# sync.net
KiCad netlist of a schematic drawn in Altium Designer
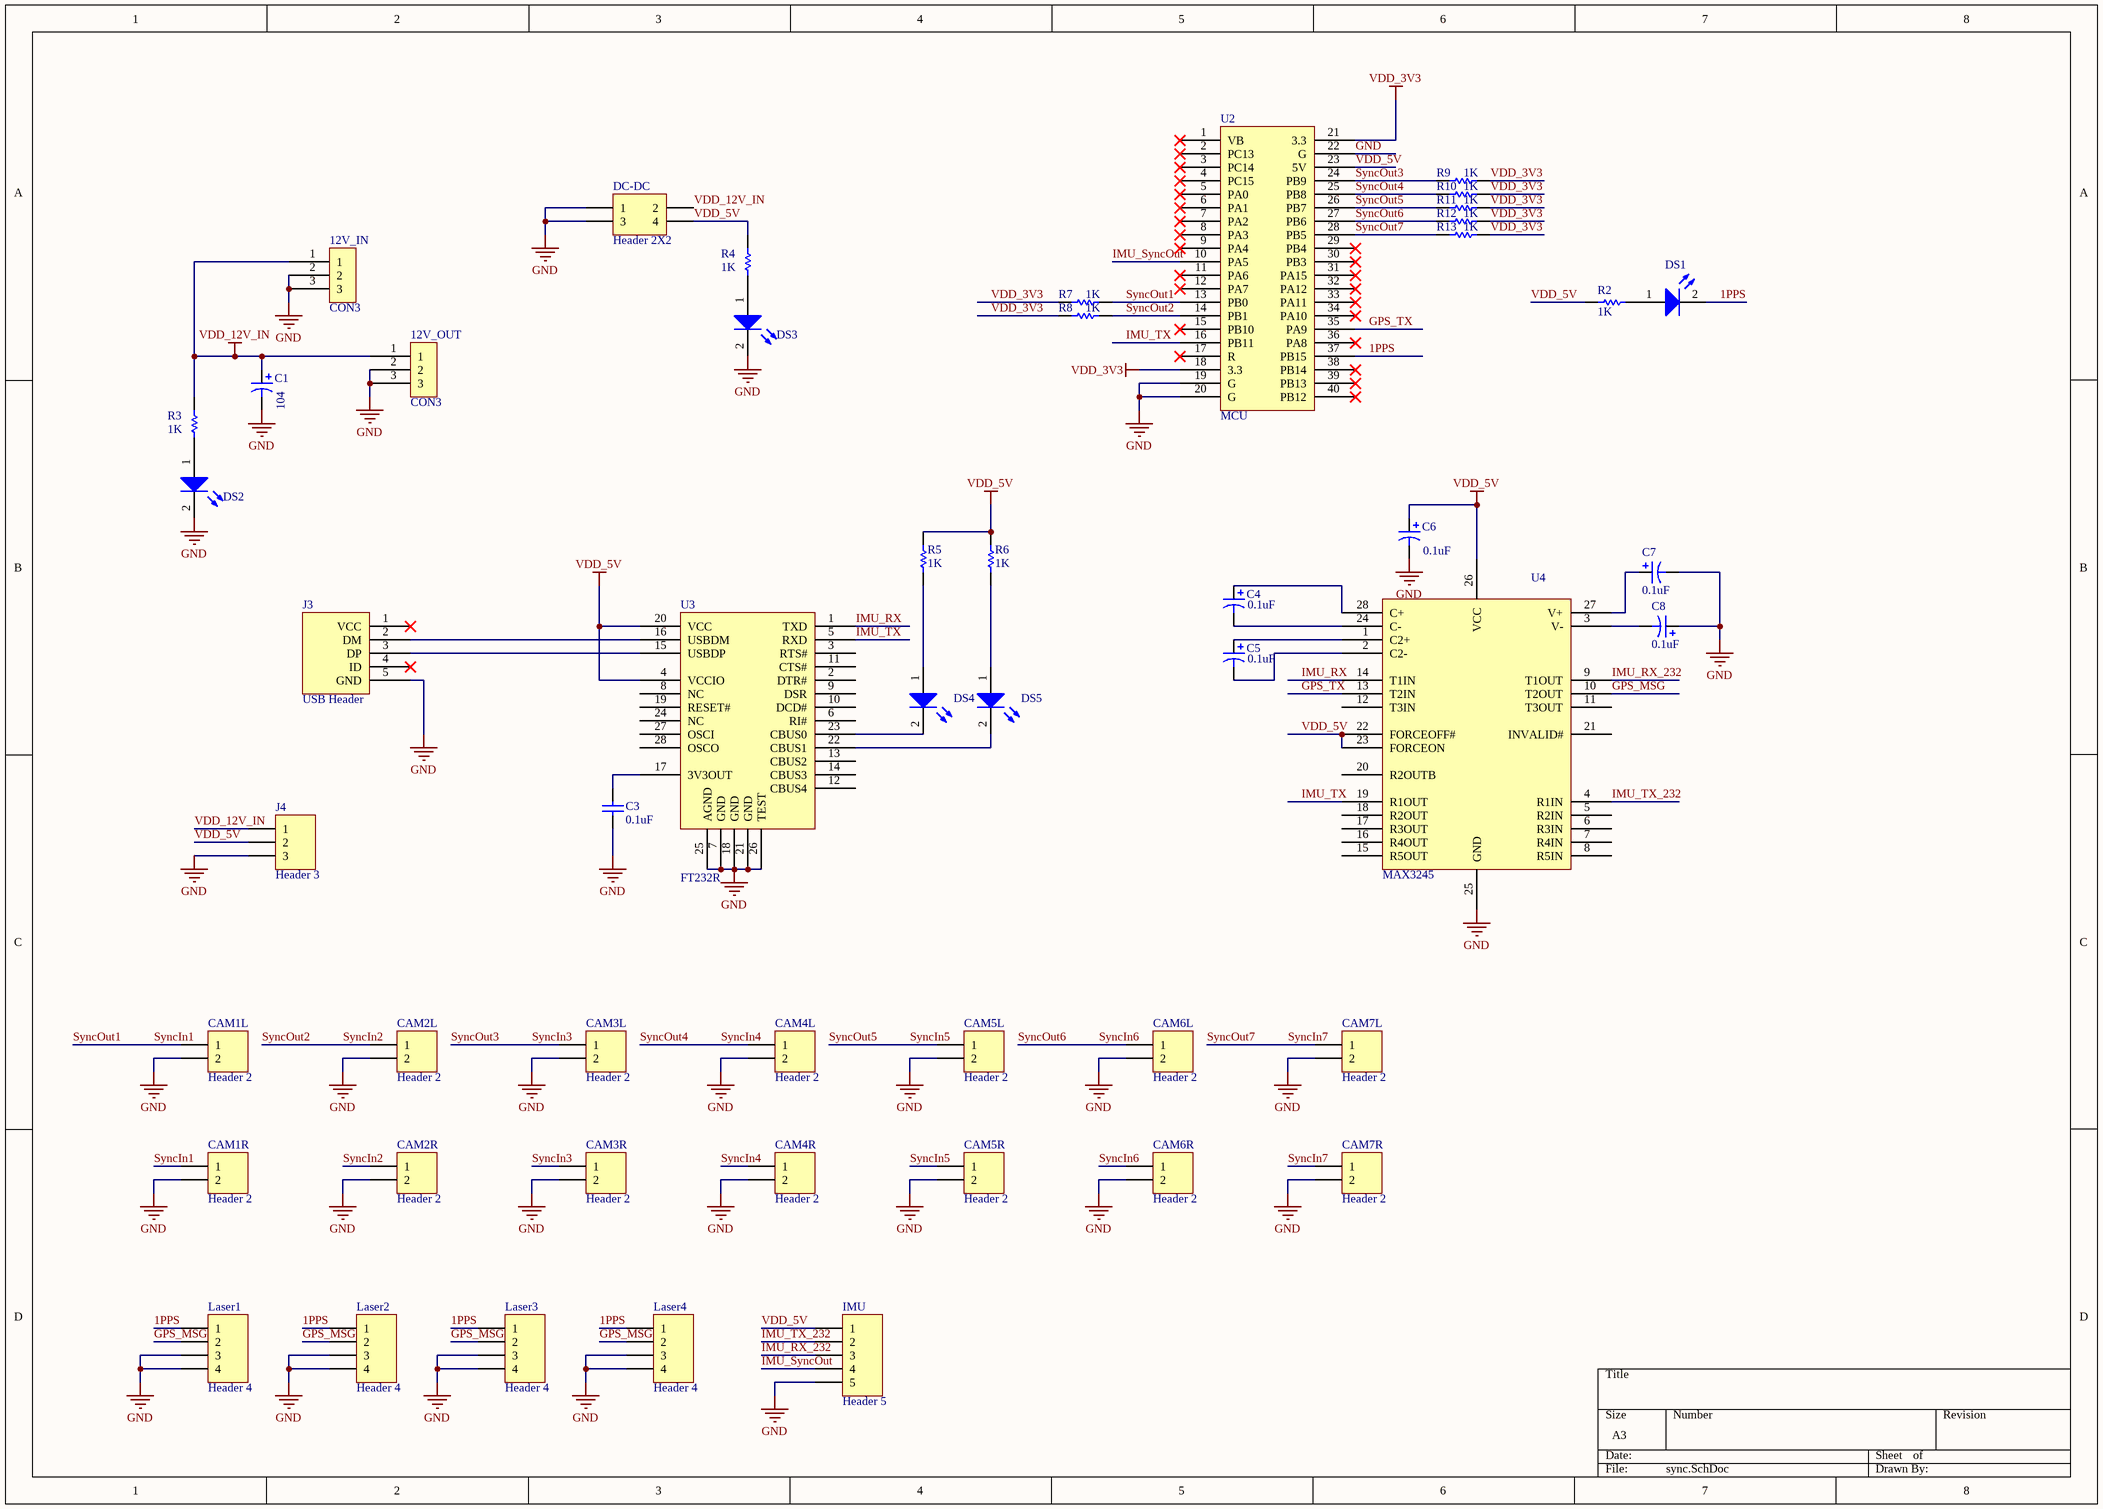
[diagram p0: sync.SchDoc]

(export (version "E")
  (design (tool "Eeschema 10.0.6"))
  (components
    (comp (ref "12V_IN")
      (value "CON3")
      (footprint "PW_PORT")
      (libsource (lib "Miscellaneous Connectors") (part "CON3"))
    )
    (comp (ref "12V_OUT") (value "CON3") (footprint "PW_PORT") (libsource (lib "EP3C25") (part "CON3")))
    (comp (ref "C1")
      (value "104")
      (footprint "0805")
      (description "Polarized Capacitor (Surface Mount)")
      (fields (field (name "PUBLISHER") "Altium Limited"))
      (libsource (lib "Miscellaneous Devices") (part "Cap Pol3"))
    )
    (comp (ref "C3")
      (value "0.1uF")
      (footprint "0805C")
      (description "Capacitor")
      (fields (field (name "PUBLISHER") "Altium Limited"))
      (libsource (lib "Miscellaneous Devices") (part "Cap"))
    )
    (comp (ref "C4")
      (value "0.1uF")
      (footprint "C1206")
      (description "Polarized Capacitor (Surface Mount)")
      (fields (field (name "PUBLISHER") "Altium Limited"))
      (libsource (lib "Miscellaneous Devices") (part "Cap Pol3"))
    )
    (comp (ref "C5")
      (value "0.1uF")
      (footprint "C1206")
      (description "Polarized Capacitor (Surface Mount)")
      (fields (field (name "PUBLISHER") "Altium Limited"))
      (libsource (lib "Miscellaneous Devices") (part "Cap Pol3"))
    )
    (comp (ref "C6")
      (value "0.1uF")
      (footprint "C1206")
      (description "Polarized Capacitor (Surface Mount)")
      (fields (field (name "PUBLISHER") "Altium Limited"))
      (libsource (lib "Miscellaneous Devices") (part "Cap Pol3"))
    )
    (comp (ref "C7")
      (value "0.1uF")
      (footprint "C1206")
      (description "Polarized Capacitor (Surface Mount)")
      (fields (field (name "PUBLISHER") "Altium Limited"))
      (libsource (lib "Miscellaneous Devices") (part "Cap Pol3"))
    )
    (comp (ref "C8")
      (value "0.1uF")
      (footprint "C1206")
      (description "Polarized Capacitor (Surface Mount)")
      (fields (field (name "PUBLISHER") "Altium Limited"))
      (libsource (lib "Miscellaneous Devices") (part "Cap Pol3"))
    )
    (comp (ref "CAM1L")
      (value "Header 2")
      (footprint "1.25mmP2")
      (description "Header, 2-Pin")
      (fields (field (name "PUBLISHER") "Altium Limited"))
      (libsource (lib "Miscellaneous Connectors") (part "Header 2"))
    )
    (comp (ref "CAM1R")
      (value "Header 2")
      (footprint "1.25mmP2")
      (description "Header, 2-Pin")
      (fields (field (name "PUBLISHER") "Altium Limited"))
      (libsource (lib "Miscellaneous Connectors") (part "Header 2"))
    )
    (comp (ref "CAM2L")
      (value "Header 2")
      (footprint "1.25mmP2")
      (description "Header, 2-Pin")
      (fields (field (name "PUBLISHER") "Altium Limited"))
      (libsource (lib "Miscellaneous Connectors") (part "Header 2"))
    )
    (comp (ref "CAM2R")
      (value "Header 2")
      (footprint "1.25mmP2")
      (description "Header, 2-Pin")
      (fields (field (name "PUBLISHER") "Altium Limited"))
      (libsource (lib "Miscellaneous Connectors") (part "Header 2"))
    )
    (comp (ref "CAM3L")
      (value "Header 2")
      (footprint "1.25mmP2")
      (description "Header, 2-Pin")
      (fields (field (name "PUBLISHER") "Altium Limited"))
      (libsource (lib "Miscellaneous Connectors") (part "Header 2"))
    )
    (comp (ref "CAM3R")
      (value "Header 2")
      (footprint "1.25mmP2")
      (description "Header, 2-Pin")
      (fields (field (name "PUBLISHER") "Altium Limited"))
      (libsource (lib "Miscellaneous Connectors") (part "Header 2"))
    )
    (comp (ref "CAM4L")
      (value "Header 2")
      (footprint "1.25mmP2")
      (description "Header, 2-Pin")
      (fields (field (name "PUBLISHER") "Altium Limited"))
      (libsource (lib "Miscellaneous Connectors") (part "Header 2"))
    )
    (comp (ref "CAM4R")
      (value "Header 2")
      (footprint "1.25mmP2")
      (description "Header, 2-Pin")
      (fields (field (name "PUBLISHER") "Altium Limited"))
      (libsource (lib "Miscellaneous Connectors") (part "Header 2"))
    )
    (comp (ref "CAM5L")
      (value "Header 2")
      (footprint "1.25mmP2")
      (description "Header, 2-Pin")
      (fields (field (name "PUBLISHER") "Altium Limited"))
      (libsource (lib "Miscellaneous Connectors") (part "Header 2"))
    )
    (comp (ref "CAM5R")
      (value "Header 2")
      (footprint "1.25mmP2")
      (description "Header, 2-Pin")
      (fields (field (name "PUBLISHER") "Altium Limited"))
      (libsource (lib "Miscellaneous Connectors") (part "Header 2"))
    )
    (comp (ref "CAM6L")
      (value "Header 2")
      (footprint "1.25mmP2")
      (description "Header, 2-Pin")
      (fields (field (name "PUBLISHER") "Altium Limited"))
      (libsource (lib "Miscellaneous Connectors") (part "Header 2"))
    )
    (comp (ref "CAM6R")
      (value "Header 2")
      (footprint "1.25mmP2")
      (description "Header, 2-Pin")
      (fields (field (name "PUBLISHER") "Altium Limited"))
      (libsource (lib "Miscellaneous Connectors") (part "Header 2"))
    )
    (comp (ref "CAM7L")
      (value "Header 2")
      (footprint "1.25mmP2")
      (description "Header, 2-Pin")
      (fields (field (name "PUBLISHER") "Altium Limited"))
      (libsource (lib "Miscellaneous Connectors") (part "Header 2"))
    )
    (comp (ref "CAM7R")
      (value "Header 2")
      (footprint "1.25mmP2")
      (description "Header, 2-Pin")
      (fields (field (name "PUBLISHER") "Altium Limited"))
      (libsource (lib "Miscellaneous Connectors") (part "Header 2"))
    )
    (comp (ref "DC-DC")
      (value "Header 2X2")
      (footprint "DC-DC5V_HDR2*2")
      (description "Header, 2-Pin, Dual row")
      (fields (field (name "PUBLISHER") "Altium Limited"))
      (libsource (lib "Miscellaneous Connectors") (part "Header 2X2"))
    )
    (comp (ref "DS1")
      (value "LED2")
      (footprint "0805D")
      (description "Typical RED, GREEN, YELLOW, AMBER GaAs LED")
      (fields
        (field (name "MANUFACTURER") "Generic Components")
        (field (name "PUBLISHER") "Altium Hobart Technology Centre")
      )
      (libsource (lib "Miscellaneous Devices") (part "LED2"))
    )
    (comp (ref "DS2")
      (value "LED2")
      (footprint "0805D")
      (description "Typical RED, GREEN, YELLOW, AMBER GaAs LED")
      (fields
        (field (name "MANUFACTURER") "Generic Components")
        (field (name "PUBLISHER") "Altium Hobart Technology Centre")
      )
      (libsource (lib "Miscellaneous Devices") (part "LED2"))
    )
    (comp (ref "DS3")
      (value "LED2")
      (footprint "0805D")
      (description "Typical RED, GREEN, YELLOW, AMBER GaAs LED")
      (fields
        (field (name "MANUFACTURER") "Generic Components")
        (field (name "PUBLISHER") "Altium Hobart Technology Centre")
      )
      (libsource (lib "Miscellaneous Devices") (part "LED2"))
    )
    (comp (ref "DS4")
      (value "LED2")
      (footprint "0805D")
      (description "Typical RED, GREEN, YELLOW, AMBER GaAs LED")
      (fields
        (field (name "MANUFACTURER") "Generic Components")
        (field (name "PUBLISHER") "Altium Hobart Technology Centre")
      )
      (libsource (lib "Miscellaneous Devices") (part "LED2"))
    )
    (comp (ref "DS5")
      (value "LED2")
      (footprint "0805D")
      (description "Typical RED, GREEN, YELLOW, AMBER GaAs LED")
      (fields
        (field (name "MANUFACTURER") "Generic Components")
        (field (name "PUBLISHER") "Altium Hobart Technology Centre")
      )
      (libsource (lib "Miscellaneous Devices") (part "LED2"))
    )
    (comp (ref "IMU")
      (value "Header 5")
      (footprint "1.25mmP5")
      (description "Header, 5-Pin")
      (fields (field (name "PUBLISHER") "Altium Limited"))
      (libsource (lib "Miscellaneous Connectors") (part "Header 5"))
    )
    (comp (ref "J3") (value "USB Header") (footprint "USB0.65-5") (libsource (lib "USB") (part "USB")))
    (comp (ref "J4")
      (value "Header 3")
      (footprint "HDR1X3")
      (description "Header, 3-Pin")
      (fields (field (name "PUBLISHER") "Altium Limited"))
      (libsource (lib "Miscellaneous Connectors") (part "Header 3"))
    )
    (comp (ref "Laser1")
      (value "Header 4")
      (footprint "1.25mmP4")
      (description "Header, 4-Pin")
      (fields (field (name "PUBLISHER") "Altium Limited"))
      (libsource (lib "Miscellaneous Connectors") (part "Header 4"))
    )
    (comp (ref "Laser2")
      (value "Header 4")
      (footprint "1.25mmP4")
      (description "Header, 4-Pin")
      (fields (field (name "PUBLISHER") "Altium Limited"))
      (libsource (lib "Miscellaneous Connectors") (part "Header 4"))
    )
    (comp (ref "Laser3")
      (value "Header 4")
      (footprint "1.25mmP4")
      (description "Header, 4-Pin")
      (fields (field (name "PUBLISHER") "Altium Limited"))
      (libsource (lib "Miscellaneous Connectors") (part "Header 4"))
    )
    (comp (ref "Laser4")
      (value "Header 4")
      (footprint "1.25mmP4")
      (description "Header, 4-Pin")
      (fields (field (name "PUBLISHER") "Altium Limited"))
      (libsource (lib "Miscellaneous Connectors") (part "Header 4"))
    )
    (comp (ref "R2")
      (value "1K")
      (footprint "0805R")
      (description "Resistor")
      (fields
        (field (name "MANUFACTURER") "Generic Components")
        (field (name "PUBLISHER") "Altium Hobart Technology Centre")
      )
      (libsource (lib "HAIBAO_MEGAV1.0_1") (part "Res1"))
    )
    (comp (ref "R3")
      (value "1K")
      (footprint "0805R")
      (description "Resistor")
      (fields
        (field (name "MANUFACTURER") "Generic Components")
        (field (name "PUBLISHER") "Altium Hobart Technology Centre")
      )
      (libsource (lib "HAIBAO_MEGAV1.0_1") (part "Res1"))
    )
    (comp (ref "R4")
      (value "1K")
      (footprint "0805R")
      (description "Resistor")
      (fields
        (field (name "MANUFACTURER") "Generic Components")
        (field (name "PUBLISHER") "Altium Hobart Technology Centre")
      )
      (libsource (lib "HAIBAO_MEGAV1.0_1") (part "Res1"))
    )
    (comp (ref "R5")
      (value "1K")
      (footprint "0805R")
      (description "Resistor")
      (fields
        (field (name "MANUFACTURER") "Generic Components")
        (field (name "PUBLISHER") "Altium Hobart Technology Centre")
      )
      (libsource (lib "HAIBAO_MEGAV1.0_1") (part "Res1"))
    )
    (comp (ref "R6")
      (value "1K")
      (footprint "0805R")
      (description "Resistor")
      (fields
        (field (name "MANUFACTURER") "Generic Components")
        (field (name "PUBLISHER") "Altium Hobart Technology Centre")
      )
      (libsource (lib "HAIBAO_MEGAV1.0_1") (part "Res1"))
    )
    (comp (ref "R7")
      (value "1K")
      (footprint "0805R")
      (description "Resistor")
      (fields
        (field (name "MANUFACTURER") "Generic Components")
        (field (name "PUBLISHER") "Altium Hobart Technology Centre")
      )
      (libsource (lib "HAIBAO_MEGAV1.0_1") (part "Res1"))
    )
    (comp (ref "R8")
      (value "1K")
      (footprint "0805R")
      (description "Resistor")
      (fields
        (field (name "MANUFACTURER") "Generic Components")
        (field (name "PUBLISHER") "Altium Hobart Technology Centre")
      )
      (libsource (lib "HAIBAO_MEGAV1.0_1") (part "Res1"))
    )
    (comp (ref "R9")
      (value "1K")
      (footprint "0805R")
      (description "Resistor")
      (fields
        (field (name "MANUFACTURER") "Generic Components")
        (field (name "PUBLISHER") "Altium Hobart Technology Centre")
      )
      (libsource (lib "HAIBAO_MEGAV1.0_1") (part "Res1"))
    )
    (comp (ref "R10")
      (value "1K")
      (footprint "0805R")
      (description "Resistor")
      (fields
        (field (name "MANUFACTURER") "Generic Components")
        (field (name "PUBLISHER") "Altium Hobart Technology Centre")
      )
      (libsource (lib "HAIBAO_MEGAV1.0_1") (part "Res1"))
    )
    (comp (ref "R11")
      (value "1K")
      (footprint "0805R")
      (description "Resistor")
      (fields
        (field (name "MANUFACTURER") "Generic Components")
        (field (name "PUBLISHER") "Altium Hobart Technology Centre")
      )
      (libsource (lib "HAIBAO_MEGAV1.0_1") (part "Res1"))
    )
    (comp (ref "R12")
      (value "1K")
      (footprint "0805R")
      (description "Resistor")
      (fields
        (field (name "MANUFACTURER") "Generic Components")
        (field (name "PUBLISHER") "Altium Hobart Technology Centre")
      )
      (libsource (lib "HAIBAO_MEGAV1.0_1") (part "Res1"))
    )
    (comp (ref "R13")
      (value "1K")
      (footprint "0805R")
      (description "Resistor")
      (fields
        (field (name "MANUFACTURER") "Generic Components")
        (field (name "PUBLISHER") "Altium Hobart Technology Centre")
      )
      (libsource (lib "HAIBAO_MEGAV1.0_1") (part "Res1"))
    )
    (comp (ref "U2") (value "MCU") (footprint "STM32Board") (libsource (lib "MCU") (part "MCU")))
    (comp (ref "U3") (value "FT232R") (footprint "SSOP-28") (libsource (lib "FT232R") (part "FT232R")))
    (comp (ref "U4") (value "MAX3245") (footprint "SSOP-28") (libsource (lib "MAX3245") (part "MAX3245")))
  )
  (nets
    (net (code "1") (name "/1PPS") (class "Default")
      (node (ref "DS1") (pin "2") (pinfunction "K_2") (pintype "passive"))
      (node (ref "Laser1") (pin "1") (pinfunction "1_1") (pintype "passive"))
      (node (ref "Laser2") (pin "1") (pinfunction "1_1") (pintype "passive"))
      (node (ref "Laser3") (pin "1") (pinfunction "1_1") (pintype "passive"))
      (node (ref "Laser4") (pin "1") (pinfunction "1_1") (pintype "passive"))
      (node (ref "U2") (pin "37") (pinfunction "PB15_37") (pintype "passive"))
    )
    (net (code "2") (name "/GPS_MSG") (class "Default")
      (node (ref "Laser1") (pin "2") (pinfunction "2_2") (pintype "passive"))
      (node (ref "Laser2") (pin "2") (pinfunction "2_2") (pintype "passive"))
      (node (ref "Laser3") (pin "2") (pinfunction "2_2") (pintype "passive"))
      (node (ref "Laser4") (pin "2") (pinfunction "2_2") (pintype "passive"))
      (node (ref "U4") (pin "10") (pinfunction "T2OUT_10") (pintype "passive"))
    )
    (net (code "3") (name "/GPS_TX") (class "Default")
      (node (ref "U2") (pin "35") (pinfunction "PA9_35") (pintype "passive"))
      (node (ref "U4") (pin "13") (pinfunction "T2IN_13") (pintype "passive"))
    )
    (net (code "4") (name "/IMU_RX") (class "Default")
      (node (ref "U3") (pin "1") (pinfunction "TXD_1") (pintype "passive"))
      (node (ref "U4") (pin "14") (pinfunction "T1IN_14") (pintype "passive"))
    )
    (net (code "5") (name "/IMU_RX_232") (class "Default")
      (node (ref "IMU") (pin "3") (pinfunction "3_3") (pintype "passive"))
      (node (ref "U4") (pin "9") (pinfunction "T1OUT_9") (pintype "passive"))
    )
    (net (code "6") (name "/IMU_SyncOut") (class "Default")
      (node (ref "IMU") (pin "4") (pinfunction "4_4") (pintype "passive"))
      (node (ref "U2") (pin "10") (pinfunction "PA5_10") (pintype "passive"))
    )
    (net (code "7") (name "/IMU_TX") (class "Default")
      (node (ref "U2") (pin "16") (pinfunction "PB11_16") (pintype "passive"))
      (node (ref "U3") (pin "5") (pinfunction "RXD_5") (pintype "passive"))
      (node (ref "U4") (pin "19") (pinfunction "R1OUT_19") (pintype "passive"))
    )
    (net (code "8") (name "/IMU_TX_232") (class "Default")
      (node (ref "IMU") (pin "2") (pinfunction "2_2") (pintype "passive"))
      (node (ref "U4") (pin "4") (pinfunction "R1IN_4") (pintype "passive"))
    )
    (net (code "9") (name "/SyncIn1") (class "Default")
      (node (ref "CAM1L") (pin "1") (pinfunction "1_1") (pintype "passive"))
      (node (ref "CAM1R") (pin "1") (pinfunction "1_1") (pintype "passive"))
      (node (ref "R7") (pin "1") (pinfunction "1_1") (pintype "passive"))
      (node (ref "U2") (pin "13") (pinfunction "PB0_13") (pintype "passive"))
    )
    (net (code "10") (name "/SyncIn2") (class "Default")
      (node (ref "CAM2L") (pin "1") (pinfunction "1_1") (pintype "passive"))
      (node (ref "CAM2R") (pin "1") (pinfunction "1_1") (pintype "passive"))
      (node (ref "R8") (pin "1") (pinfunction "1_1") (pintype "passive"))
      (node (ref "U2") (pin "14") (pinfunction "PB1_14") (pintype "passive"))
    )
    (net (code "11") (name "/SyncIn3") (class "Default")
      (node (ref "CAM3L") (pin "1") (pinfunction "1_1") (pintype "passive"))
      (node (ref "CAM3R") (pin "1") (pinfunction "1_1") (pintype "passive"))
      (node (ref "R9") (pin "2") (pinfunction "2_2") (pintype "passive"))
      (node (ref "U2") (pin "24") (pinfunction "PB9_24") (pintype "passive"))
    )
    (net (code "12") (name "/SyncIn4") (class "Default")
      (node (ref "CAM4L") (pin "1") (pinfunction "1_1") (pintype "passive"))
      (node (ref "CAM4R") (pin "1") (pinfunction "1_1") (pintype "passive"))
      (node (ref "R10") (pin "2") (pinfunction "2_2") (pintype "passive"))
      (node (ref "U2") (pin "25") (pinfunction "PB8_25") (pintype "passive"))
    )
    (net (code "13") (name "/SyncIn5") (class "Default")
      (node (ref "CAM5L") (pin "1") (pinfunction "1_1") (pintype "passive"))
      (node (ref "CAM5R") (pin "1") (pinfunction "1_1") (pintype "passive"))
      (node (ref "R11") (pin "2") (pinfunction "2_2") (pintype "passive"))
      (node (ref "U2") (pin "26") (pinfunction "PB7_26") (pintype "passive"))
    )
    (net (code "14") (name "/SyncIn6") (class "Default")
      (node (ref "CAM6L") (pin "1") (pinfunction "1_1") (pintype "passive"))
      (node (ref "CAM6R") (pin "1") (pinfunction "1_1") (pintype "passive"))
      (node (ref "R12") (pin "2") (pinfunction "2_2") (pintype "passive"))
      (node (ref "U2") (pin "27") (pinfunction "PB6_27") (pintype "passive"))
    )
    (net (code "15") (name "/SyncIn7") (class "Default")
      (node (ref "CAM7L") (pin "1") (pinfunction "1_1") (pintype "passive"))
      (node (ref "CAM7R") (pin "1") (pinfunction "1_1") (pintype "passive"))
      (node (ref "R13") (pin "2") (pinfunction "2_2") (pintype "passive"))
      (node (ref "U2") (pin "28") (pinfunction "PB5_28") (pintype "passive"))
    )
    (net (code "16") (name "GND") (class "Default")
      (node (ref "12V_IN") (pin "2") (pinfunction "2_2") (pintype "passive"))
      (node (ref "12V_IN") (pin "3") (pinfunction "3_3") (pintype "passive"))
      (node (ref "12V_OUT") (pin "2") (pinfunction "2_2") (pintype "passive"))
      (node (ref "12V_OUT") (pin "3") (pinfunction "3_3") (pintype "passive"))
      (node (ref "C1") (pin "2") (pinfunction "2_2") (pintype "passive"))
      (node (ref "C3") (pin "1") (pinfunction "1_1") (pintype "passive"))
      (node (ref "C6") (pin "2") (pinfunction "2_2") (pintype "passive"))
      (node (ref "C7") (pin "2") (pinfunction "2_2") (pintype "passive"))
      (node (ref "C8") (pin "1") (pinfunction "1_1") (pintype "passive"))
      (node (ref "CAM1L") (pin "2") (pinfunction "2_2") (pintype "passive"))
      (node (ref "CAM1R") (pin "2") (pinfunction "2_2") (pintype "passive"))
      (node (ref "CAM2L") (pin "2") (pinfunction "2_2") (pintype "passive"))
      (node (ref "CAM2R") (pin "2") (pinfunction "2_2") (pintype "passive"))
      (node (ref "CAM3L") (pin "2") (pinfunction "2_2") (pintype "passive"))
      (node (ref "CAM3R") (pin "2") (pinfunction "2_2") (pintype "passive"))
      (node (ref "CAM4L") (pin "2") (pinfunction "2_2") (pintype "passive"))
      (node (ref "CAM4R") (pin "2") (pinfunction "2_2") (pintype "passive"))
      (node (ref "CAM5L") (pin "2") (pinfunction "2_2") (pintype "passive"))
      (node (ref "CAM5R") (pin "2") (pinfunction "2_2") (pintype "passive"))
      (node (ref "CAM6L") (pin "2") (pinfunction "2_2") (pintype "passive"))
      (node (ref "CAM6R") (pin "2") (pinfunction "2_2") (pintype "passive"))
      (node (ref "CAM7L") (pin "2") (pinfunction "2_2") (pintype "passive"))
      (node (ref "CAM7R") (pin "2") (pinfunction "2_2") (pintype "passive"))
      (node (ref "DC-DC") (pin "1") (pinfunction "1_1") (pintype "passive"))
      (node (ref "DC-DC") (pin "3") (pinfunction "3_3") (pintype "passive"))
      (node (ref "DS2") (pin "2") (pinfunction "K_2") (pintype "passive"))
      (node (ref "DS3") (pin "2") (pinfunction "K_2") (pintype "passive"))
      (node (ref "IMU") (pin "5") (pinfunction "5_5") (pintype "passive"))
      (node (ref "J3") (pin "5") (pinfunction "GND_5") (pintype "passive"))
      (node (ref "J4") (pin "3") (pinfunction "3_3") (pintype "passive"))
      (node (ref "Laser1") (pin "3") (pinfunction "3_3") (pintype "passive"))
      (node (ref "Laser1") (pin "4") (pinfunction "4_4") (pintype "passive"))
      (node (ref "Laser2") (pin "3") (pinfunction "3_3") (pintype "passive"))
      (node (ref "Laser2") (pin "4") (pinfunction "4_4") (pintype "passive"))
      (node (ref "Laser3") (pin "3") (pinfunction "3_3") (pintype "passive"))
      (node (ref "Laser3") (pin "4") (pinfunction "4_4") (pintype "passive"))
      (node (ref "Laser4") (pin "3") (pinfunction "3_3") (pintype "passive"))
      (node (ref "Laser4") (pin "4") (pinfunction "4_4") (pintype "passive"))
      (node (ref "U2") (pin "19") (pinfunction "G_19") (pintype "passive"))
      (node (ref "U2") (pin "20") (pinfunction "G_20") (pintype "passive"))
      (node (ref "U2") (pin "22") (pinfunction "G_22") (pintype "passive"))
      (node (ref "U3") (pin "18") (pinfunction "GND_18") (pintype "passive"))
      (node (ref "U3") (pin "21") (pinfunction "GND_21") (pintype "passive"))
      (node (ref "U3") (pin "25") (pinfunction "AGND_25") (pintype "passive"))
      (node (ref "U3") (pin "26") (pinfunction "TEST_26") (pintype "passive"))
      (node (ref "U3") (pin "7") (pinfunction "GND_7") (pintype "passive"))
      (node (ref "U4") (pin "25") (pinfunction "GND_25") (pintype "passive"))
    )
    (net (code "17") (name "Net-(DS1-A)") (class "Default")
      (node (ref "DS1") (pin "1") (pinfunction "A_1") (pintype "passive"))
      (node (ref "R2") (pin "1") (pinfunction "1_1") (pintype "passive"))
    )
    (net (code "18") (name "Net-(DS2-A)") (class "Default")
      (node (ref "DS2") (pin "1") (pinfunction "A_1") (pintype "passive"))
      (node (ref "R3") (pin "1") (pinfunction "1_1") (pintype "passive"))
    )
    (net (code "19") (name "Net-(DS3-A)") (class "Default")
      (node (ref "DS3") (pin "1") (pinfunction "A_1") (pintype "passive"))
      (node (ref "R4") (pin "1") (pinfunction "1_1") (pintype "passive"))
    )
    (net (code "20") (name "Net-(DS4-A)") (class "Default")
      (node (ref "DS4") (pin "1") (pinfunction "A_1") (pintype "passive"))
      (node (ref "R5") (pin "2") (pinfunction "2_2") (pintype "passive"))
    )
    (net (code "21") (name "Net-(DS4-K)") (class "Default")
      (node (ref "DS4") (pin "2") (pinfunction "K_2") (pintype "passive"))
      (node (ref "U3") (pin "23") (pinfunction "CBUS0_23") (pintype "passive"))
    )
    (net (code "22") (name "Net-(DS5-A)") (class "Default")
      (node (ref "DS5") (pin "1") (pinfunction "A_1") (pintype "passive"))
      (node (ref "R6") (pin "2") (pinfunction "2_2") (pintype "passive"))
    )
    (net (code "23") (name "Net-(DS5-K)") (class "Default")
      (node (ref "DS5") (pin "2") (pinfunction "K_2") (pintype "passive"))
      (node (ref "U3") (pin "22") (pinfunction "CBUS1_22") (pintype "passive"))
    )
    (net (code "24") (name "Net-(J3-DM)") (class "Default")
      (node (ref "J3") (pin "2") (pinfunction "DM_2") (pintype "passive"))
      (node (ref "U3") (pin "16") (pinfunction "USBDM_16") (pintype "passive"))
    )
    (net (code "25") (name "Net-(J3-DP)") (class "Default")
      (node (ref "J3") (pin "3") (pinfunction "DP_3") (pintype "passive"))
      (node (ref "U3") (pin "15") (pinfunction "USBDP_15") (pintype "passive"))
    )
    (net (code "26") (name "Net-(U3-3V3OUT)") (class "Default")
      (node (ref "C3") (pin "2") (pinfunction "2_2") (pintype "passive"))
      (node (ref "U3") (pin "17") (pinfunction "3V3OUT_17") (pintype "passive"))
    )
    (net (code "27") (name "Net-(U4-C+)") (class "Default")
      (node (ref "C4") (pin "1") (pinfunction "1_1") (pintype "passive"))
      (node (ref "U4") (pin "28") (pinfunction "C+_28") (pintype "passive"))
    )
    (net (code "28") (name "Net-(U4-C-)") (class "Default")
      (node (ref "C4") (pin "2") (pinfunction "2_2") (pintype "passive"))
      (node (ref "U4") (pin "24") (pinfunction "C-_24") (pintype "passive"))
    )
    (net (code "29") (name "Net-(U4-C2+)") (class "Default")
      (node (ref "C5") (pin "1") (pinfunction "1_1") (pintype "passive"))
      (node (ref "U4") (pin "1") (pinfunction "C2+_1") (pintype "passive"))
    )
    (net (code "30") (name "Net-(U4-C2-)") (class "Default")
      (node (ref "C5") (pin "2") (pinfunction "2_2") (pintype "passive"))
      (node (ref "U4") (pin "2") (pinfunction "C2-_2") (pintype "passive"))
    )
    (net (code "31") (name "Net-(U4-V+)") (class "Default")
      (node (ref "C7") (pin "1") (pinfunction "1_1") (pintype "passive"))
      (node (ref "U4") (pin "27") (pinfunction "V+_27") (pintype "passive"))
    )
    (net (code "32") (name "Net-(U4-V-)") (class "Default")
      (node (ref "C8") (pin "2") (pinfunction "2_2") (pintype "passive"))
      (node (ref "U4") (pin "3") (pinfunction "V-_3") (pintype "passive"))
    )
    (net (code "33") (name "VDD_3V3") (class "Default")
      (node (ref "R10") (pin "1") (pinfunction "1_1") (pintype "passive"))
      (node (ref "R11") (pin "1") (pinfunction "1_1") (pintype "passive"))
      (node (ref "R12") (pin "1") (pinfunction "1_1") (pintype "passive"))
      (node (ref "R13") (pin "1") (pinfunction "1_1") (pintype "passive"))
      (node (ref "R7") (pin "2") (pinfunction "2_2") (pintype "passive"))
      (node (ref "R8") (pin "2") (pinfunction "2_2") (pintype "passive"))
      (node (ref "R9") (pin "1") (pinfunction "1_1") (pintype "passive"))
      (node (ref "U2") (pin "18") (pinfunction "3.3_18") (pintype "passive"))
      (node (ref "U2") (pin "21") (pinfunction "3.3_21") (pintype "passive"))
    )
    (net (code "34") (name "VDD_5V") (class "Default")
      (node (ref "C6") (pin "1") (pinfunction "1_1") (pintype "passive"))
      (node (ref "DC-DC") (pin "4") (pinfunction "4_4") (pintype "passive"))
      (node (ref "IMU") (pin "1") (pinfunction "1_1") (pintype "passive"))
      (node (ref "J4") (pin "2") (pinfunction "2_2") (pintype "passive"))
      (node (ref "R2") (pin "2") (pinfunction "2_2") (pintype "passive"))
      (node (ref "R4") (pin "2") (pinfunction "2_2") (pintype "passive"))
      (node (ref "R5") (pin "1") (pinfunction "1_1") (pintype "passive"))
      (node (ref "R6") (pin "1") (pinfunction "1_1") (pintype "passive"))
      (node (ref "U2") (pin "23") (pinfunction "5V_23") (pintype "passive"))
      (node (ref "U3") (pin "20") (pinfunction "VCC_20") (pintype "passive"))
      (node (ref "U3") (pin "4") (pinfunction "VCCIO_4") (pintype "passive"))
      (node (ref "U4") (pin "22") (pinfunction "FORCEOFF#_22") (pintype "passive"))
      (node (ref "U4") (pin "23") (pinfunction "FORCEON_23") (pintype "passive"))
      (node (ref "U4") (pin "26") (pinfunction "VCC_26") (pintype "passive"))
    )
    (net (code "35") (name "VDD_12V_IN") (class "Default")
      (node (ref "12V_IN") (pin "1") (pinfunction "1_1") (pintype "passive"))
      (node (ref "12V_OUT") (pin "1") (pinfunction "1_1") (pintype "passive"))
      (node (ref "C1") (pin "1") (pinfunction "1_1") (pintype "passive"))
      (node (ref "DC-DC") (pin "2") (pinfunction "2_2") (pintype "passive"))
      (node (ref "J4") (pin "1") (pinfunction "1_1") (pintype "passive"))
      (node (ref "R3") (pin "2") (pinfunction "2_2") (pintype "passive"))
    )
    (net (code "36") (name "unconnected-(J3-ID-Pad4)") (class "Default")
      (node (ref "J3") (pin "4") (pinfunction "ID_4") (pintype "passive+no_connect"))
    )
    (net (code "37") (name "unconnected-(J3-VCC-Pad1)") (class "Default")
      (node (ref "J3") (pin "1") (pinfunction "VCC_1") (pintype "passive+no_connect"))
    )
    (net (code "38") (name "unconnected-(U2-PA0-Pad5)") (class "Default")
      (node (ref "U2") (pin "5") (pinfunction "PA0_5") (pintype "passive+no_connect"))
    )
    (net (code "39") (name "unconnected-(U2-PA1-Pad6)") (class "Default")
      (node (ref "U2") (pin "6") (pinfunction "PA1_6") (pintype "passive+no_connect"))
    )
    (net (code "40") (name "unconnected-(U2-PA2-Pad7)") (class "Default")
      (node (ref "U2") (pin "7") (pinfunction "PA2_7") (pintype "passive+no_connect"))
    )
    (net (code "41") (name "unconnected-(U2-PA3-Pad8)") (class "Default")
      (node (ref "U2") (pin "8") (pinfunction "PA3_8") (pintype "passive+no_connect"))
    )
    (net (code "42") (name "unconnected-(U2-PA4-Pad9)") (class "Default")
      (node (ref "U2") (pin "9") (pinfunction "PA4_9") (pintype "passive+no_connect"))
    )
    (net (code "43") (name "unconnected-(U2-PA6-Pad11)") (class "Default")
      (node (ref "U2") (pin "11") (pinfunction "PA6_11") (pintype "passive+no_connect"))
    )
    (net (code "44") (name "unconnected-(U2-PA7-Pad12)") (class "Default")
      (node (ref "U2") (pin "12") (pinfunction "PA7_12") (pintype "passive+no_connect"))
    )
    (net (code "45") (name "unconnected-(U2-PA8-Pad36)") (class "Default")
      (node (ref "U2") (pin "36") (pinfunction "PA8_36") (pintype "passive+no_connect"))
    )
    (net (code "46") (name "unconnected-(U2-PA10-Pad34)") (class "Default")
      (node (ref "U2") (pin "34") (pinfunction "PA10_34") (pintype "passive+no_connect"))
    )
    (net (code "47") (name "unconnected-(U2-PA11-Pad33)") (class "Default")
      (node (ref "U2") (pin "33") (pinfunction "PA11_33") (pintype "passive+no_connect"))
    )
    (net (code "48") (name "unconnected-(U2-PA12-Pad32)") (class "Default")
      (node (ref "U2") (pin "32") (pinfunction "PA12_32") (pintype "passive+no_connect"))
    )
    (net (code "49") (name "unconnected-(U2-PA15-Pad31)") (class "Default")
      (node (ref "U2") (pin "31") (pinfunction "PA15_31") (pintype "passive+no_connect"))
    )
    (net (code "50") (name "unconnected-(U2-PB3-Pad30)") (class "Default")
      (node (ref "U2") (pin "30") (pinfunction "PB3_30") (pintype "passive+no_connect"))
    )
    (net (code "51") (name "unconnected-(U2-PB4-Pad29)") (class "Default")
      (node (ref "U2") (pin "29") (pinfunction "PB4_29") (pintype "passive+no_connect"))
    )
    (net (code "52") (name "unconnected-(U2-PB10-Pad15)") (class "Default")
      (node (ref "U2") (pin "15") (pinfunction "PB10_15") (pintype "passive+no_connect"))
    )
    (net (code "53") (name "unconnected-(U2-PB12-Pad40)") (class "Default")
      (node (ref "U2") (pin "40") (pinfunction "PB12_40") (pintype "passive+no_connect"))
    )
    (net (code "54") (name "unconnected-(U2-PB13-Pad39)") (class "Default")
      (node (ref "U2") (pin "39") (pinfunction "PB13_39") (pintype "passive+no_connect"))
    )
    (net (code "55") (name "unconnected-(U2-PB14-Pad38)") (class "Default")
      (node (ref "U2") (pin "38") (pinfunction "PB14_38") (pintype "passive+no_connect"))
    )
    (net (code "56") (name "unconnected-(U2-PC13-Pad2)") (class "Default")
      (node (ref "U2") (pin "2") (pinfunction "PC13_2") (pintype "passive+no_connect"))
    )
    (net (code "57") (name "unconnected-(U2-PC14-Pad3)") (class "Default")
      (node (ref "U2") (pin "3") (pinfunction "PC14_3") (pintype "passive+no_connect"))
    )
    (net (code "58") (name "unconnected-(U2-PC15-Pad4)") (class "Default")
      (node (ref "U2") (pin "4") (pinfunction "PC15_4") (pintype "passive+no_connect"))
    )
    (net (code "59") (name "unconnected-(U2-R-Pad17)") (class "Default")
      (node (ref "U2") (pin "17") (pinfunction "R_17") (pintype "passive+no_connect"))
    )
    (net (code "60") (name "unconnected-(U2-VB-Pad1)") (class "Default")
      (node (ref "U2") (pin "1") (pinfunction "VB_1") (pintype "power_in+no_connect"))
    )
    (net (code "61") (name "unconnected-(U3-CBUS2-Pad13)") (class "Default")
      (node (ref "U3") (pin "13") (pinfunction "CBUS2_13") (pintype "passive"))
    )
    (net (code "62") (name "unconnected-(U3-CBUS3-Pad14)") (class "Default")
      (node (ref "U3") (pin "14") (pinfunction "CBUS3_14") (pintype "passive"))
    )
    (net (code "63") (name "unconnected-(U3-CBUS4-Pad12)") (class "Default")
      (node (ref "U3") (pin "12") (pinfunction "CBUS4_12") (pintype "passive"))
    )
    (net (code "64") (name "unconnected-(U3-CTS#-Pad11)") (class "Default")
      (node (ref "U3") (pin "11") (pinfunction "CTS#_11") (pintype "passive"))
    )
    (net (code "65") (name "unconnected-(U3-DCD#-Pad10)") (class "Default")
      (node (ref "U3") (pin "10") (pinfunction "DCD#_10") (pintype "passive"))
    )
    (net (code "66") (name "unconnected-(U3-DSR-Pad9)") (class "Default")
      (node (ref "U3") (pin "9") (pinfunction "DSR_9") (pintype "passive"))
    )
    (net (code "67") (name "unconnected-(U3-DTR#-Pad2)") (class "Default")
      (node (ref "U3") (pin "2") (pinfunction "DTR#_2") (pintype "passive"))
    )
    (net (code "68") (name "unconnected-(U3-NC-Pad8)") (class "Default")
      (node (ref "U3") (pin "8") (pinfunction "NC_8") (pintype "passive"))
    )
    (net (code "69") (name "unconnected-(U3-NC-Pad24)") (class "Default")
      (node (ref "U3") (pin "24") (pinfunction "NC_24") (pintype "passive"))
    )
    (net (code "70") (name "unconnected-(U3-OSCI-Pad27)") (class "Default")
      (node (ref "U3") (pin "27") (pinfunction "OSCI_27") (pintype "passive"))
    )
    (net (code "71") (name "unconnected-(U3-OSCO-Pad28)") (class "Default")
      (node (ref "U3") (pin "28") (pinfunction "OSCO_28") (pintype "passive"))
    )
    (net (code "72") (name "unconnected-(U3-RESET#-Pad19)") (class "Default")
      (node (ref "U3") (pin "19") (pinfunction "RESET#_19") (pintype "passive"))
    )
    (net (code "73") (name "unconnected-(U3-RI#-Pad6)") (class "Default")
      (node (ref "U3") (pin "6") (pinfunction "RI#_6") (pintype "passive"))
    )
    (net (code "74") (name "unconnected-(U3-RTS#-Pad3)") (class "Default")
      (node (ref "U3") (pin "3") (pinfunction "RTS#_3") (pintype "passive"))
    )
    (net (code "75") (name "unconnected-(U4-INVALID#-Pad21)") (class "Default")
      (node (ref "U4") (pin "21") (pinfunction "INVALID#_21") (pintype "passive"))
    )
    (net (code "76") (name "unconnected-(U4-R2IN-Pad5)") (class "Default")
      (node (ref "U4") (pin "5") (pinfunction "R2IN_5") (pintype "passive"))
    )
    (net (code "77") (name "unconnected-(U4-R2OUT-Pad18)") (class "Default")
      (node (ref "U4") (pin "18") (pinfunction "R2OUT_18") (pintype "passive"))
    )
    (net (code "78") (name "unconnected-(U4-R2OUTB-Pad20)") (class "Default")
      (node (ref "U4") (pin "20") (pinfunction "R2OUTB_20") (pintype "passive"))
    )
    (net (code "79") (name "unconnected-(U4-R3IN-Pad6)") (class "Default")
      (node (ref "U4") (pin "6") (pinfunction "R3IN_6") (pintype "passive"))
    )
    (net (code "80") (name "unconnected-(U4-R3OUT-Pad17)") (class "Default")
      (node (ref "U4") (pin "17") (pinfunction "R3OUT_17") (pintype "passive"))
    )
    (net (code "81") (name "unconnected-(U4-R4IN-Pad7)") (class "Default")
      (node (ref "U4") (pin "7") (pinfunction "R4IN_7") (pintype "passive"))
    )
    (net (code "82") (name "unconnected-(U4-R4OUT-Pad16)") (class "Default")
      (node (ref "U4") (pin "16") (pinfunction "R4OUT_16") (pintype "passive"))
    )
    (net (code "83") (name "unconnected-(U4-R5IN-Pad8)") (class "Default")
      (node (ref "U4") (pin "8") (pinfunction "R5IN_8") (pintype "passive"))
    )
    (net (code "84") (name "unconnected-(U4-R5OUT-Pad15)") (class "Default")
      (node (ref "U4") (pin "15") (pinfunction "R5OUT_15") (pintype "passive"))
    )
    (net (code "85") (name "unconnected-(U4-T3IN-Pad12)") (class "Default")
      (node (ref "U4") (pin "12") (pinfunction "T3IN_12") (pintype "passive"))
    )
    (net (code "86") (name "unconnected-(U4-T3OUT-Pad11)") (class "Default")
      (node (ref "U4") (pin "11") (pinfunction "T3OUT_11") (pintype "passive"))
    )
  )
)
